# LilyPad_XBee.net
KiCad netlist of a schematic drawn in EAGLE
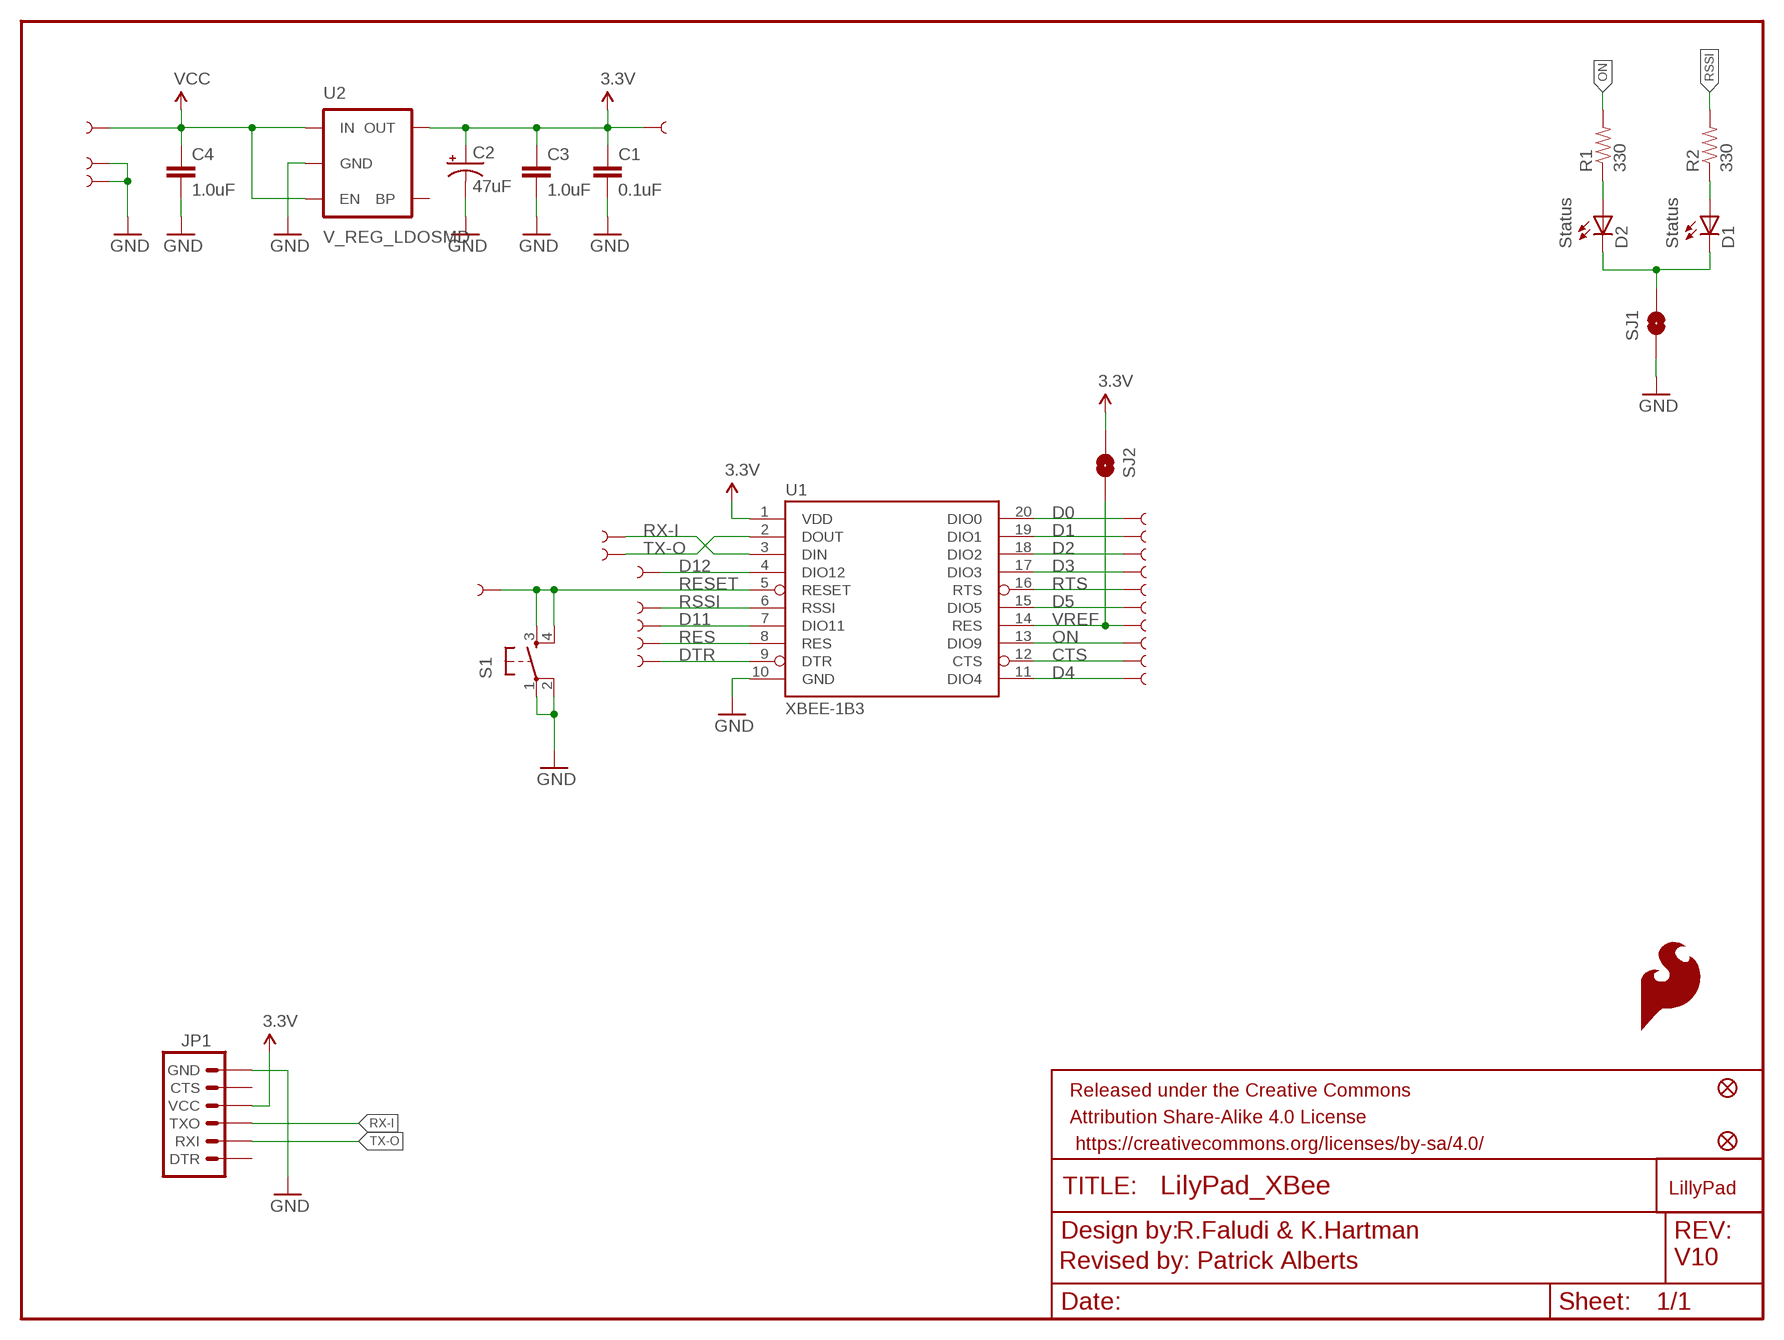
[diagram p0: schematic, sheet 1]

(export (version "E")
  (design (tool "Eeschema 10.0.6"))
  (components
    (comp (ref "C1")
      (value "0.1uF")
      (footprint "eagle-import:0603-CAP")
      (libsource (lib "eagle-import") (part "0.1UF-25V(+80/-20%)(0603)"))
    )
    (comp (ref "C2")
      (value "47uF")
      (footprint "eagle-import:EIA3528")
      (libsource (lib "eagle-import") (part "CAP_POL3528"))
    )
    (comp (ref "C3")
      (value "1.0uF")
      (footprint "eagle-import:0603-CAP")
      (libsource (lib "eagle-import") (part "1.0UF-16V-10%(0603)"))
    )
    (comp (ref "C4")
      (value "1.0uF")
      (footprint "eagle-import:0603-CAP")
      (libsource (lib "eagle-import") (part "1.0UF-16V-10%(0603)"))
    )
    (comp (ref "D1")
      (value "Status")
      (footprint "eagle-import:LED-0603")
      (libsource (lib "eagle-import") (part "LED-GREEN0603"))
    )
    (comp (ref "D2")
      (value "Status")
      (footprint "eagle-import:LED-0603")
      (libsource (lib "eagle-import") (part "LED-RED0603"))
    )
    (comp (ref "FID1")
      (value "FIDUCIAL1X2")
      (footprint "eagle-import:FIDUCIAL-1X2")
      (libsource (lib "eagle-import") (part "FIDUCIAL1X2"))
    )
    (comp (ref "FID2")
      (value "FIDUCIAL1X2")
      (footprint "eagle-import:FIDUCIAL-1X2")
      (libsource (lib "eagle-import") (part "FIDUCIAL1X2"))
    )
    (comp (ref "FRAME1")
      (value "FRAME-LETTER")
      (footprint "eagle-import:CREATIVE_COMMONS")
      (libsource (lib "eagle-import") (part "FRAME-LETTER"))
    )
    (comp (ref "GND")
      (value "SEWTAP9")
      (footprint "eagle-import:PETAL-LONG-1-2SIDE")
      (libsource (lib "eagle-import") (part "SEWTAP9"))
    )
    (comp (ref "JP1")
      (value "ARDUINO_SERIAL_PROGRAMPTH")
      (footprint "eagle-import:1X06")
      (libsource (lib "eagle-import") (part "ARDUINO_SERIAL_PROGRAMPTH"))
    )
    (comp (ref "LOGO1")
      (value "SFE_LOGO_FLAME.1COP")
      (footprint "eagle-import:SFE_LOGO_FLAME_COPPER_.1")
      (libsource (lib "eagle-import") (part "SFE_LOGO_FLAME.1COP"))
    )
    (comp (ref "R1")
      (value "330")
      (footprint "eagle-import:0603-RES")
      (libsource (lib "eagle-import") (part "330OHM1/10W1%(0603)"))
    )
    (comp (ref "R2")
      (value "330")
      (footprint "eagle-import:0603-RES")
      (libsource (lib "eagle-import") (part "330OHM1/10W1%(0603)"))
    )
    (comp (ref "S1")
      (value "TAC_SWITCHSMD")
      (footprint "eagle-import:TACTILE_SWITCH_SMD")
      (libsource (lib "eagle-import") (part "TAC_SWITCHSMD"))
    )
    (comp (ref "SJ1")
      (value "SOLDERJUMPERNC2")
      (footprint "eagle-import:SJ_2S-NOTRACE")
      (libsource (lib "eagle-import") (part "SOLDERJUMPERNC2"))
    )
    (comp (ref "SJ2")
      (value "SOLDERJUMPERNC2")
      (footprint "eagle-import:SJ_2S-NOTRACE")
      (libsource (lib "eagle-import") (part "SOLDERJUMPERNC2"))
    )
    (comp (ref "U$1")
      (value "LOGO-LPLP")
      (footprint "eagle-import:LOGO-LILYPAD")
      (libsource (lib "eagle-import") (part "LOGO-LPLP"))
    )
    (comp (ref "U$4")
      (value "SEWTAP9")
      (footprint "eagle-import:PETAL-LONG-1-2SIDE")
      (libsource (lib "eagle-import") (part "SEWTAP9"))
    )
    (comp (ref "U$30")
      (value "SEWTAP9")
      (footprint "eagle-import:PETAL-LONG-1-2SIDE")
      (libsource (lib "eagle-import") (part "SEWTAP9"))
    )
    (comp (ref "U$31")
      (value "SEWTAP9")
      (footprint "eagle-import:PETAL-LONG-1-2SIDE")
      (libsource (lib "eagle-import") (part "SEWTAP9"))
    )
    (comp (ref "U$32")
      (value "SEWTAP9")
      (footprint "eagle-import:PETAL-LONG-1-2SIDE")
      (libsource (lib "eagle-import") (part "SEWTAP9"))
    )
    (comp (ref "U$33")
      (value "SEWTAP9")
      (footprint "eagle-import:PETAL-LONG-1-2SIDE")
      (libsource (lib "eagle-import") (part "SEWTAP9"))
    )
    (comp (ref "U$34")
      (value "SEWTAP9")
      (footprint "eagle-import:PETAL-LONG-1-2SIDE")
      (libsource (lib "eagle-import") (part "SEWTAP9"))
    )
    (comp (ref "U$35")
      (value "SEWTAP9")
      (footprint "eagle-import:PETAL-LONG-1-2SIDE")
      (libsource (lib "eagle-import") (part "SEWTAP9"))
    )
    (comp (ref "U$36")
      (value "SEWTAP9")
      (footprint "eagle-import:PETAL-LONG-1-2SIDE")
      (libsource (lib "eagle-import") (part "SEWTAP9"))
    )
    (comp (ref "U$37")
      (value "SEWTAP9")
      (footprint "eagle-import:PETAL-LONG-1-2SIDE")
      (libsource (lib "eagle-import") (part "SEWTAP9"))
    )
    (comp (ref "U$38")
      (value "SEWTAP9")
      (footprint "eagle-import:PETAL-LONG-1-2SIDE")
      (libsource (lib "eagle-import") (part "SEWTAP9"))
    )
    (comp (ref "U$39")
      (value "SEWTAP9")
      (footprint "eagle-import:PETAL-LONG-1-2SIDE")
      (libsource (lib "eagle-import") (part "SEWTAP9"))
    )
    (comp (ref "U$40")
      (value "SEWTAP9")
      (footprint "eagle-import:PETAL-LONG-1-2SIDE")
      (libsource (lib "eagle-import") (part "SEWTAP9"))
    )
    (comp (ref "U$41")
      (value "SEWTAP9")
      (footprint "eagle-import:PETAL-LONG-1-2SIDE")
      (libsource (lib "eagle-import") (part "SEWTAP9"))
    )
    (comp (ref "U$42")
      (value "SEWTAP9")
      (footprint "eagle-import:PETAL-LONG-1-2SIDE")
      (libsource (lib "eagle-import") (part "SEWTAP9"))
    )
    (comp (ref "U$43")
      (value "SEWTAP9")
      (footprint "eagle-import:PETAL-LONG-1-2SIDE")
      (libsource (lib "eagle-import") (part "SEWTAP9"))
    )
    (comp (ref "U$44")
      (value "SEWTAP9")
      (footprint "eagle-import:PETAL-LONG-1-2SIDE")
      (libsource (lib "eagle-import") (part "SEWTAP9"))
    )
    (comp (ref "U$45")
      (value "SEWTAP9")
      (footprint "eagle-import:PETAL-LONG-1-2SIDE")
      (libsource (lib "eagle-import") (part "SEWTAP9"))
    )
    (comp (ref "U$46")
      (value "SEWTAP9")
      (footprint "eagle-import:PETAL-LONG-1-2SIDE")
      (libsource (lib "eagle-import") (part "SEWTAP9"))
    )
    (comp (ref "U$47")
      (value "SEWTAP9")
      (footprint "eagle-import:PETAL-LONG-1-2SIDE")
      (libsource (lib "eagle-import") (part "SEWTAP9"))
    )
    (comp (ref "U$48")
      (value "SEWTAP9")
      (footprint "eagle-import:PETAL-LONG-1-2SIDE")
      (libsource (lib "eagle-import") (part "SEWTAP9"))
    )
    (comp (ref "U$51")
      (value "SEWTAP9")
      (footprint "eagle-import:PETAL-LONG-1-2SIDE")
      (libsource (lib "eagle-import") (part "SEWTAP9"))
    )
    (comp (ref "U1")
      (value "XBEE-1B3")
      (footprint "eagle-import:XBEE-SMD")
      (libsource (lib "eagle-import") (part "XBEE-1B3"))
    )
    (comp (ref "U2")
      (value "V_REG_LDOSMD")
      (footprint "eagle-import:SOT23-5")
      (libsource (lib "eagle-import") (part "V_REG_LDOSMD"))
    )
  )
  (nets
    (net (code "1") (name "/CTS") (class "Default")
      (node (ref "U$38") (pin "1") (pinfunction "1_1") (pintype "bidirectional"))
      (node (ref "U1") (pin "12") (pinfunction "CTS_12") (pintype "output"))
    )
    (net (code "2") (name "/D0") (class "Default")
      (node (ref "U$34") (pin "1") (pinfunction "1_1") (pintype "bidirectional"))
      (node (ref "U1") (pin "20") (pinfunction "DIO0_20") (pintype "bidirectional"))
    )
    (net (code "3") (name "/D1") (class "Default")
      (node (ref "U$33") (pin "1") (pinfunction "1_1") (pintype "bidirectional"))
      (node (ref "U1") (pin "19") (pinfunction "DIO1_19") (pintype "bidirectional"))
    )
    (net (code "4") (name "/D2") (class "Default")
      (node (ref "U$32") (pin "1") (pinfunction "1_1") (pintype "bidirectional"))
      (node (ref "U1") (pin "18") (pinfunction "DIO2_18") (pintype "bidirectional"))
    )
    (net (code "5") (name "/D3") (class "Default")
      (node (ref "U$31") (pin "1") (pinfunction "1_1") (pintype "bidirectional"))
      (node (ref "U1") (pin "17") (pinfunction "DIO3_17") (pintype "bidirectional"))
    )
    (net (code "6") (name "/D4") (class "Default")
      (node (ref "U$37") (pin "1") (pinfunction "1_1") (pintype "bidirectional"))
      (node (ref "U1") (pin "11") (pinfunction "DIO4_11") (pintype "bidirectional"))
    )
    (net (code "7") (name "/D5") (class "Default")
      (node (ref "U$4") (pin "1") (pinfunction "1_1") (pintype "bidirectional"))
      (node (ref "U1") (pin "15") (pinfunction "DIO5_15") (pintype "bidirectional"))
    )
    (net (code "8") (name "/D11") (class "Default")
      (node (ref "U$42") (pin "1") (pinfunction "1_1") (pintype "bidirectional"))
      (node (ref "U1") (pin "7") (pinfunction "DIO11_7") (pintype "bidirectional"))
    )
    (net (code "9") (name "/D12") (class "Default")
      (node (ref "U$43") (pin "1") (pinfunction "1_1") (pintype "bidirectional"))
      (node (ref "U1") (pin "4") (pinfunction "DIO12_4") (pintype "bidirectional"))
    )
    (net (code "10") (name "/DTR") (class "Default")
      (node (ref "U$48") (pin "1") (pinfunction "1_1") (pintype "bidirectional"))
      (node (ref "U1") (pin "9") (pinfunction "DTR_9") (pintype "bidirectional"))
    )
    (net (code "11") (name "/RES") (class "Default")
      (node (ref "U$41") (pin "1") (pinfunction "1_1") (pintype "bidirectional"))
      (node (ref "U1") (pin "8") (pinfunction "RES_8") (pintype "bidirectional"))
    )
    (net (code "12") (name "/RESET") (class "Default")
      (node (ref "GND") (pin "1") (pinfunction "1_1") (pintype "bidirectional"))
      (node (ref "S1") (pin "3") (pinfunction "3_3") (pintype "passive"))
      (node (ref "S1") (pin "4") (pinfunction "4_4") (pintype "passive"))
      (node (ref "U1") (pin "5") (pinfunction "RESET_5") (pintype "input"))
    )
    (net (code "13") (name "/RTS") (class "Default")
      (node (ref "U$30") (pin "1") (pinfunction "1_1") (pintype "bidirectional"))
      (node (ref "U1") (pin "16") (pinfunction "RTS_16") (pintype "input"))
    )
    (net (code "14") (name "/VREF") (class "Default")
      (node (ref "SJ2") (pin "2") (pinfunction "2_2") (pintype "passive"))
      (node (ref "U$40") (pin "1") (pinfunction "1_1") (pintype "bidirectional"))
      (node (ref "U1") (pin "14") (pinfunction "RES_14") (pintype "bidirectional"))
    )
    (net (code "15") (name "3.3V") (class "Default")
      (node (ref "C1") (pin "1") (pinfunction "1_1") (pintype "passive"))
      (node (ref "C2") (pin "A") (pinfunction "+_A") (pintype "passive"))
      (node (ref "C3") (pin "1") (pinfunction "1_1") (pintype "passive"))
      (node (ref "JP1") (pin "4") (pinfunction "VCC_4") (pintype "passive"))
      (node (ref "SJ2") (pin "1") (pinfunction "1_1") (pintype "passive"))
      (node (ref "U$47") (pin "1") (pinfunction "1_1") (pintype "bidirectional"))
      (node (ref "U1") (pin "1") (pinfunction "VDD_1") (pintype "power_in"))
      (node (ref "U2") (pin "5") (pinfunction "OUT_5") (pintype "passive"))
    )
    (net (code "16") (name "GND") (class "Default")
      (node (ref "C1") (pin "2") (pinfunction "2_2") (pintype "passive"))
      (node (ref "C2") (pin "C") (pinfunction "-_C") (pintype "passive"))
      (node (ref "C3") (pin "2") (pinfunction "2_2") (pintype "passive"))
      (node (ref "C4") (pin "2") (pinfunction "2_2") (pintype "passive"))
      (node (ref "JP1") (pin "6") (pinfunction "GND_6") (pintype "passive"))
      (node (ref "S1") (pin "1") (pinfunction "1_1") (pintype "passive"))
      (node (ref "S1") (pin "2") (pinfunction "2_2") (pintype "passive"))
      (node (ref "SJ1") (pin "1") (pinfunction "1_1") (pintype "passive"))
      (node (ref "U$36") (pin "1") (pinfunction "1_1") (pintype "bidirectional"))
      (node (ref "U$46") (pin "1") (pinfunction "1_1") (pintype "bidirectional"))
      (node (ref "U1") (pin "10") (pinfunction "GND_10") (pintype "power_in"))
      (node (ref "U2") (pin "2") (pinfunction "GND_2") (pintype "input"))
    )
    (net (code "17") (name "Net-(D1-PadA)") (class "Default")
      (node (ref "D1") (pin "A") (pinfunction "A_A") (pintype "passive"))
      (node (ref "R2") (pin "1") (pinfunction "1_1") (pintype "passive"))
    )
    (net (code "18") (name "Net-(D1-PadC)") (class "Default")
      (node (ref "D1") (pin "C") (pinfunction "C_C") (pintype "passive"))
      (node (ref "D2") (pin "C") (pinfunction "C_C") (pintype "passive"))
      (node (ref "SJ1") (pin "2") (pinfunction "2_2") (pintype "passive"))
    )
    (net (code "19") (name "Net-(D2-PadA)") (class "Default")
      (node (ref "D2") (pin "A") (pinfunction "A_A") (pintype "passive"))
      (node (ref "R1") (pin "1") (pinfunction "1_1") (pintype "passive"))
    )
    (net (code "20") (name "ON") (class "Default")
      (node (ref "R1") (pin "2") (pinfunction "2_2") (pintype "passive"))
      (node (ref "U$39") (pin "1") (pinfunction "1_1") (pintype "bidirectional"))
      (node (ref "U1") (pin "13") (pinfunction "DIO9_13") (pintype "bidirectional"))
    )
    (net (code "21") (name "RSSI") (class "Default")
      (node (ref "R2") (pin "2") (pinfunction "2_2") (pintype "passive"))
      (node (ref "U$51") (pin "1") (pinfunction "1_1") (pintype "bidirectional"))
      (node (ref "U1") (pin "6") (pinfunction "RSSI_6") (pintype "bidirectional"))
    )
    (net (code "22") (name "RX-I") (class "Default")
      (node (ref "JP1") (pin "3") (pinfunction "TXO_3") (pintype "passive"))
      (node (ref "U$45") (pin "1") (pinfunction "1_1") (pintype "bidirectional"))
      (node (ref "U1") (pin "3") (pinfunction "DIN_3") (pintype "input"))
    )
    (net (code "23") (name "TX-O") (class "Default")
      (node (ref "JP1") (pin "2") (pinfunction "RXI_2") (pintype "passive"))
      (node (ref "U$44") (pin "1") (pinfunction "1_1") (pintype "bidirectional"))
      (node (ref "U1") (pin "2") (pinfunction "DOUT_2") (pintype "output"))
    )
    (net (code "24") (name "VCC") (class "Default")
      (node (ref "C4") (pin "1") (pinfunction "1_1") (pintype "passive"))
      (node (ref "U$35") (pin "1") (pinfunction "1_1") (pintype "bidirectional"))
      (node (ref "U2") (pin "1") (pinfunction "IN_1") (pintype "input"))
      (node (ref "U2") (pin "3") (pinfunction "EN_3") (pintype "input"))
    )
    (net (code "25") (name "unconnected-(JP1-CTS-Pad5)") (class "Default")
      (node (ref "JP1") (pin "5") (pinfunction "CTS_5") (pintype "passive"))
    )
    (net (code "26") (name "unconnected-(JP1-DTR-Pad1)") (class "Default")
      (node (ref "JP1") (pin "1") (pinfunction "DTR_1") (pintype "passive"))
    )
    (net (code "27") (name "unconnected-(U2-BP-Pad4)") (class "Default")
      (node (ref "U2") (pin "4") (pinfunction "BP_4") (pintype "input"))
    )
  )
)
